# mikro.net
KiCad netlist of a schematic drawn in Altium Designer
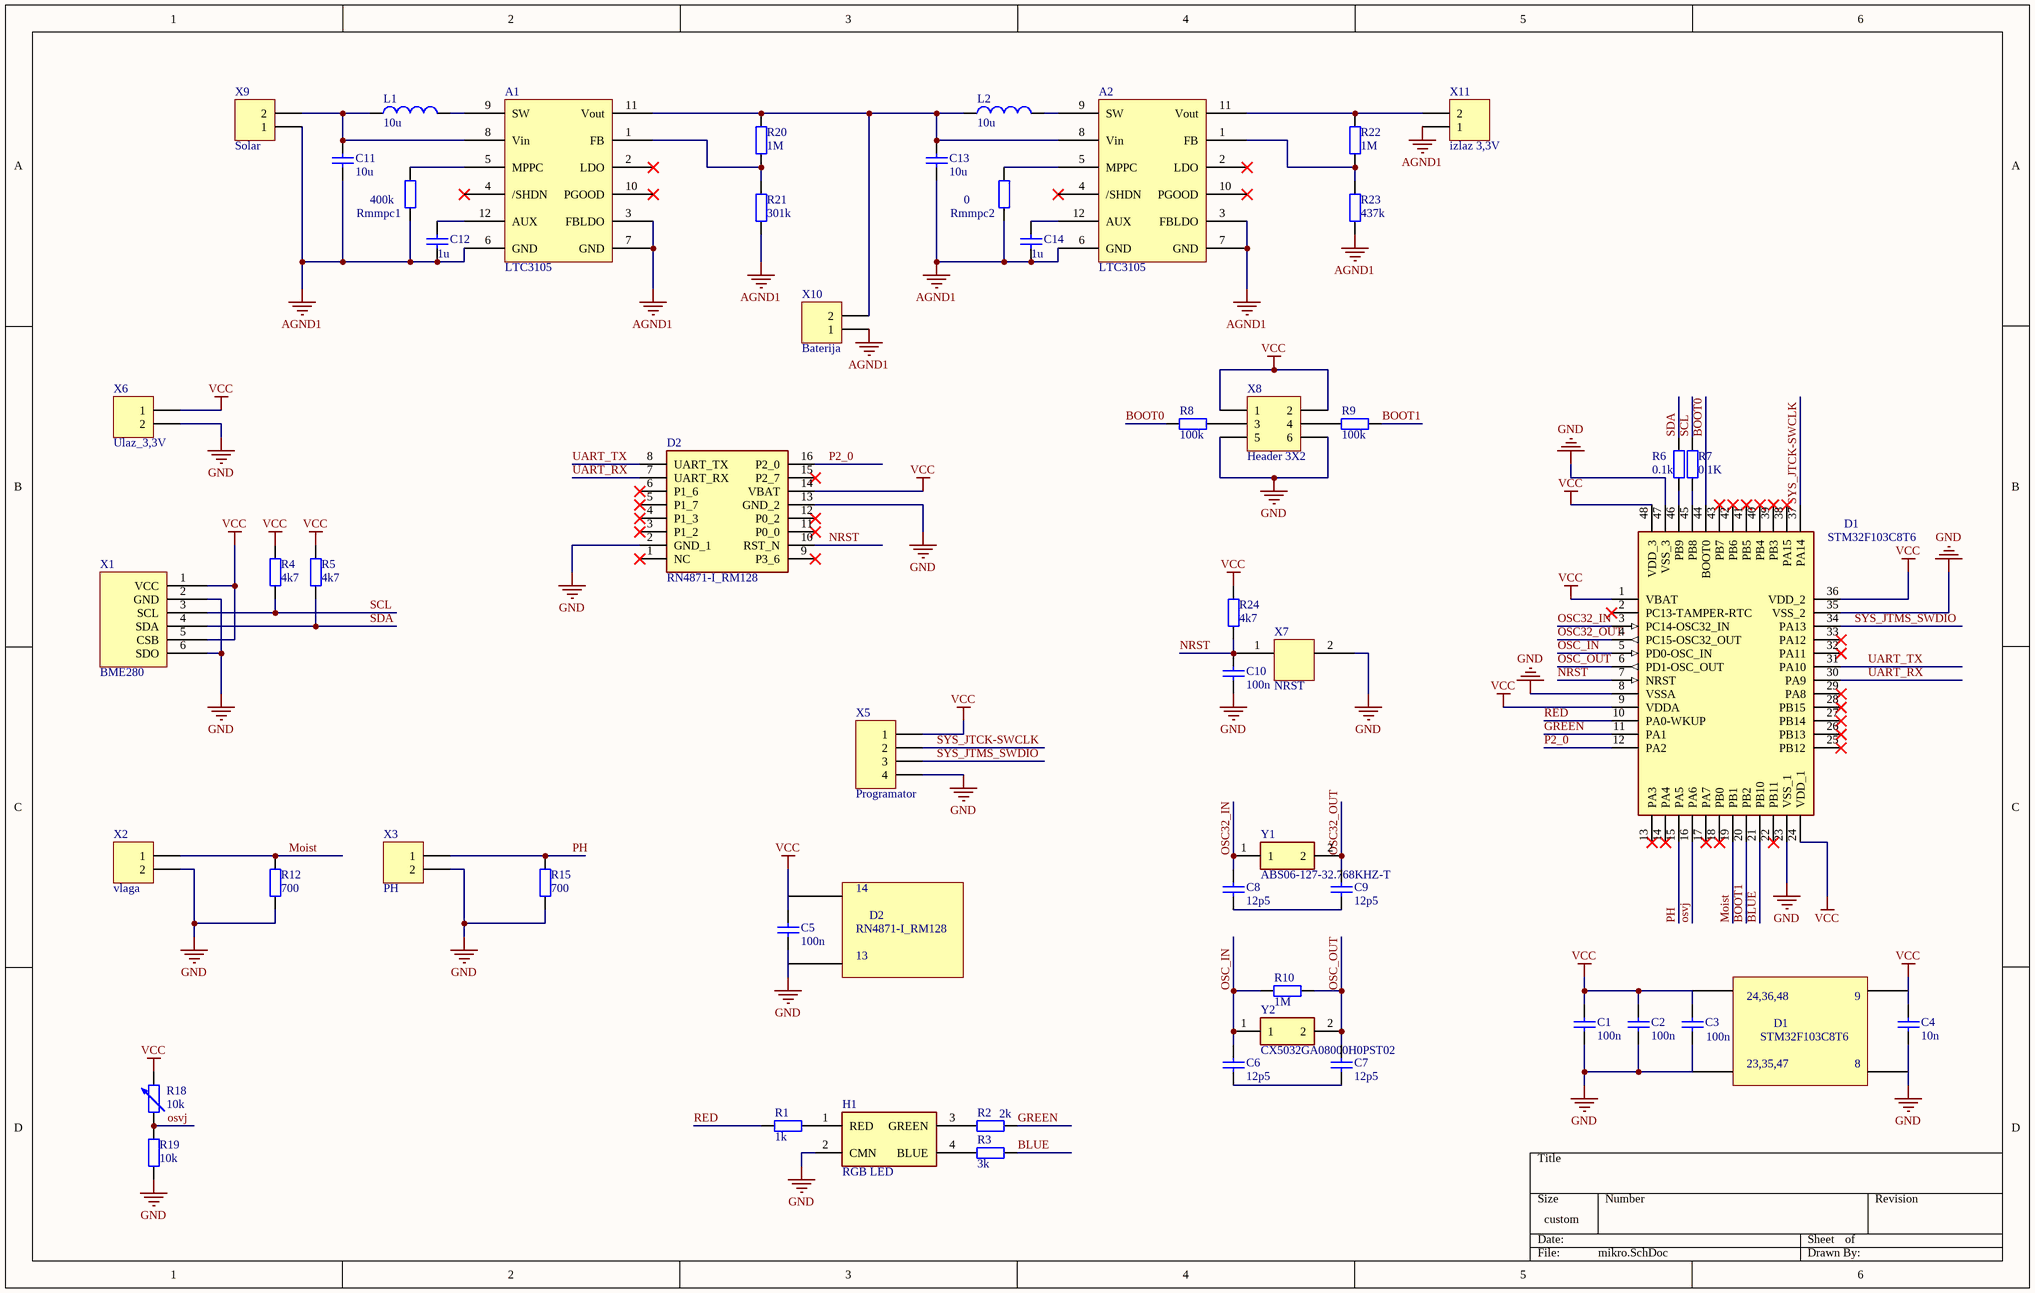
[diagram p0: mikro.SchDoc]

(export (version "E")
  (design (tool "Eeschema 10.0.6"))
  (components
    (comp (ref "A1")
      (value "LTC3105")
      (footprint "SOP65P490X110-12N")
      (libsource (lib "altium-import") (part "root_0_LTC3105_"))
    )
    (comp (ref "A2")
      (value "LTC3105")
      (footprint "SOP65P490X110-12N")
      (libsource (lib "altium-import") (part "root_0_LTC3105_"))
    )
    (comp (ref "C1")
      (value "100n")
      (footprint "6-0805_N")
      (description "Capacitor")
      (fields (field (name "PUBLISHER") "Altium Limited"))
      (libsource (lib "Miscellaneous Devices") (part "Cap"))
    )
    (comp (ref "C2")
      (value "100n")
      (footprint "6-0805_N")
      (description "Capacitor")
      (fields (field (name "PUBLISHER") "Altium Limited"))
      (libsource (lib "Miscellaneous Devices") (part "Cap"))
    )
    (comp (ref "C3")
      (value "100n")
      (footprint "6-0805_N")
      (description "Capacitor")
      (fields (field (name "PUBLISHER") "Altium Limited"))
      (libsource (lib "Miscellaneous Devices") (part "Cap"))
    )
    (comp (ref "C4")
      (value "10n")
      (footprint "6-0805_N")
      (description "Capacitor")
      (fields (field (name "PUBLISHER") "Altium Limited"))
      (libsource (lib "Miscellaneous Devices") (part "Cap"))
    )
    (comp (ref "C5")
      (value "100n")
      (footprint "6-0805_N")
      (description "Capacitor")
      (fields (field (name "PUBLISHER") "Altium Limited"))
      (libsource (lib "Miscellaneous Devices") (part "Cap"))
    )
    (comp (ref "C6")
      (value "12p5")
      (footprint "6-0805_N")
      (description "Capacitor")
      (fields (field (name "PUBLISHER") "Altium Limited"))
      (libsource (lib "Miscellaneous Devices") (part "Cap"))
    )
    (comp (ref "C7")
      (value "12p5")
      (footprint "6-0805_N")
      (description "Capacitor")
      (fields (field (name "PUBLISHER") "Altium Limited"))
      (libsource (lib "Miscellaneous Devices") (part "Cap"))
    )
    (comp (ref "C8")
      (value "12p5")
      (footprint "6-0805_N")
      (description "Capacitor")
      (fields (field (name "PUBLISHER") "Altium Limited"))
      (libsource (lib "Miscellaneous Devices") (part "Cap"))
    )
    (comp (ref "C9")
      (value "12p5")
      (footprint "6-0805_N")
      (description "Capacitor")
      (fields (field (name "PUBLISHER") "Altium Limited"))
      (libsource (lib "Miscellaneous Devices") (part "Cap"))
    )
    (comp (ref "C10")
      (value "100n")
      (footprint "6-0805_N")
      (description "Capacitor")
      (fields (field (name "PUBLISHER") "Altium Limited"))
      (libsource (lib "Miscellaneous Devices") (part "Cap"))
    )
    (comp (ref "C11")
      (value "10u")
      (footprint "6-0805_N")
      (description "Capacitor")
      (fields (field (name "PUBLISHER") "Altium Limited"))
      (libsource (lib "Miscellaneous Devices") (part "Cap"))
    )
    (comp (ref "C12")
      (value "1u")
      (footprint "6-0805_N")
      (description "Capacitor")
      (fields (field (name "PUBLISHER") "Altium Limited"))
      (libsource (lib "Miscellaneous Devices") (part "Cap"))
    )
    (comp (ref "C13")
      (value "10u")
      (footprint "6-0805_N")
      (description "Capacitor")
      (fields (field (name "PUBLISHER") "Altium Limited"))
      (libsource (lib "Miscellaneous Devices") (part "Cap"))
    )
    (comp (ref "C14")
      (value "1u")
      (footprint "6-0805_N")
      (description "Capacitor")
      (fields (field (name "PUBLISHER") "Altium Limited"))
      (libsource (lib "Miscellaneous Devices") (part "Cap"))
    )
    (comp (ref "D1")
      (value "STM32F103C8T6")
      (footprint "SamacSys:QFP50P900X900X160-48N")
      (description "Integrated Circuit")
      (fields
        (field (name "MOUSER PART NUMBER") "511-STM32F103C8T6")
        (field (name "RS PART NUMBER") "0402279P")
      )
      (libsource (lib "*") (part "STM32F103C8T6"))
    )
    (comp (ref "D2")
      (value "RN4871-I_RM128")
      (footprint "SamacSys:RN4871")
      (description "Integrated Circuit")
      (fields
        (field (name "MANUFACTURER_PART_NUMBER") "RN4871-I/RM128")
        (field (name "MOUSER PART NUMBER") "579-RN4871-I/RM128")
      )
      (libsource (lib "altium-import") (part "root_2_mirrored_RN4871-I_RM128_"))
    )
    (comp (ref "H1")
      (value "RGB LED")
      (footprint "HV5RGB25")
      (description "LED")
      (fields
        (field (name "MANUFACTURER_PART_NUMBER") "APTF1616LSEEZGKQBKC")
        (field (name "MOUSER PART NUMBER") "604-APTF1616LSEEZGKQ")
      )
      (libsource (lib "altium-import") (part "root_0_APTF1616LSEEZGKQBKC_"))
    )
    (comp (ref "L1")
      (value "10u")
      (footprint "6-0805_N")
      (description "Inductor")
      (fields (field (name "PUBLISHER") "Altium Limited"))
      (libsource (lib "Miscellaneous Devices") (part "Inductor"))
    )
    (comp (ref "L2")
      (value "10u")
      (footprint "6-0805_N")
      (description "Inductor")
      (fields (field (name "PUBLISHER") "Altium Limited"))
      (libsource (lib "Miscellaneous Devices") (part "Inductor"))
    )
    (comp (ref "R1")
      (value "1k")
      (footprint "6-0805_N")
      (description "Resistor")
      (fields (field (name "PUBLISHER") "Altium Limited"))
      (libsource (lib "") (part "Res2_3"))
    )
    (comp (ref "R2")
      (value "2k")
      (footprint "6-0805_N")
      (description "Resistor")
      (fields (field (name "PUBLISHER") "Altium Limited"))
      (libsource (lib "") (part "Res2_3"))
    )
    (comp (ref "R3")
      (value "3k")
      (footprint "6-0805_N")
      (description "Resistor")
      (fields (field (name "PUBLISHER") "Altium Limited"))
      (libsource (lib "") (part "Res2_3"))
    )
    (comp (ref "R4")
      (value "4k7")
      (footprint "6-0805_N")
      (description "Resistor")
      (fields (field (name "PUBLISHER") "Altium Limited"))
      (libsource (lib "") (part "Res2_1"))
    )
    (comp (ref "R5")
      (value "4k7")
      (footprint "6-0805_N")
      (description "Resistor")
      (fields (field (name "PUBLISHER") "Altium Limited"))
      (libsource (lib "") (part "Res2_1"))
    )
    (comp (ref "R6")
      (value "0.1k")
      (footprint "6-0805_N")
      (description "Resistor")
      (fields (field (name "PUBLISHER") "Altium Limited"))
      (libsource (lib "") (part "Res2_1"))
    )
    (comp (ref "R7")
      (value "0.1K")
      (footprint "6-0805_N")
      (description "Resistor")
      (fields (field (name "PUBLISHER") "Altium Limited"))
      (libsource (lib "") (part "Res2_1"))
    )
    (comp (ref "R8")
      (value "100k")
      (footprint "6-0805_N")
      (description "Resistor")
      (fields (field (name "PUBLISHER") "Altium Limited"))
      (libsource (lib "") (part "Res2_2"))
    )
    (comp (ref "R9")
      (value "100k")
      (footprint "6-0805_N")
      (description "Resistor")
      (fields (field (name "PUBLISHER") "Altium Limited"))
      (libsource (lib "") (part "Res2_2"))
    )
    (comp (ref "R10")
      (value "1M")
      (footprint "6-0805_N")
      (description "Resistor")
      (fields (field (name "PUBLISHER") "Altium Limited"))
      (libsource (lib "") (part "Res2_3"))
    )
    (comp (ref "R12")
      (value "700")
      (footprint "6-0805_N")
      (description "Resistor")
      (fields (field (name "PUBLISHER") "Altium Limited"))
      (libsource (lib "Miscellaneous Devices") (part "Res2"))
    )
    (comp (ref "R15")
      (value "700")
      (footprint "6-0805_N")
      (description "Resistor")
      (fields (field (name "PUBLISHER") "Altium Limited"))
      (libsource (lib "Miscellaneous Devices") (part "Res2"))
    )
    (comp (ref "R18")
      (value "10k")
      (footprint "HDR1X2")
      (description "Variable Resistor")
      (fields (field (name "PUBLISHER") "Altium Limited"))
      (libsource (lib "Miscellaneous Devices") (part "Res Adj2"))
    )
    (comp (ref "R19")
      (value "10k")
      (footprint "6-0805_N")
      (description "Resistor")
      (fields (field (name "PUBLISHER") "Altium Limited"))
      (libsource (lib "") (part "Res2_1"))
    )
    (comp (ref "R20")
      (value "1M")
      (footprint "6-0805_N")
      (description "Resistor")
      (fields (field (name "PUBLISHER") "Altium Limited"))
      (libsource (lib "") (part "Res2_1"))
    )
    (comp (ref "R21")
      (value "301k")
      (footprint "6-0805_N")
      (description "Resistor")
      (fields (field (name "PUBLISHER") "Altium Limited"))
      (libsource (lib "Miscellaneous Devices") (part "Res2"))
    )
    (comp (ref "R22")
      (value "1M")
      (footprint "6-0805_N")
      (description "Resistor")
      (fields (field (name "PUBLISHER") "Altium Limited"))
      (libsource (lib "") (part "Res2_1"))
    )
    (comp (ref "R23")
      (value "437k")
      (footprint "6-0805_N")
      (description "Resistor")
      (fields (field (name "PUBLISHER") "Altium Limited"))
      (libsource (lib "Miscellaneous Devices") (part "Res2"))
    )
    (comp (ref "R24")
      (value "4k7")
      (footprint "6-0805_N")
      (description "Resistor")
      (fields (field (name "PUBLISHER") "Altium Limited"))
      (libsource (lib "Miscellaneous Devices") (part "Res2"))
    )
    (comp (ref "Rmmpc1")
      (value "400k")
      (footprint "6-0805_N")
      (description "Resistor")
      (fields (field (name "PUBLISHER") "Altium Limited"))
      (libsource (lib "") (part "Res2_1"))
    )
    (comp (ref "Rmmpc2")
      (value "0")
      (footprint "6-0805_N")
      (description "Resistor")
      (fields (field (name "PUBLISHER") "Altium Limited"))
      (libsource (lib "") (part "Res2_1"))
    )
    (comp (ref "X1")
      (value "BME280")
      (footprint "HDR1X6")
      (libsource (lib "altium-import") (part "root_0_BME280_"))
    )
    (comp (ref "X2")
      (value "vlaga")
      (footprint "HDR1X2")
      (description "Header, 2-Pin")
      (fields (field (name "PUBLISHER") "Altium Limited"))
      (libsource (lib "Miscellaneous Connectors") (part "Header 2"))
    )
    (comp (ref "X3")
      (value "PH")
      (footprint "HDR1X2")
      (description "Header, 2-Pin")
      (fields (field (name "PUBLISHER") "Altium Limited"))
      (libsource (lib "Miscellaneous Connectors") (part "Header 2"))
    )
    (comp (ref "X5")
      (value "Programator")
      (footprint "HDR1X4")
      (description "Header, 4-Pin")
      (fields (field (name "PUBLISHER") "Altium Limited"))
      (libsource (lib "Miscellaneous Connectors") (part "Header 4"))
    )
    (comp (ref "X6")
      (value "Ulaz_3,3V")
      (footprint "HDR1X2")
      (description "Header, 2-Pin")
      (fields (field (name "PUBLISHER") "Altium Limited"))
      (libsource (lib "Miscellaneous Connectors") (part "Header 2"))
    )
    (comp (ref "X7") (value "NRST") (libsource (lib "altium-import") (part "root_1_jumper_")))
    (comp (ref "X8")
      (value "Header 3X2")
      (footprint "HDR2X3")
      (description "Header, 3-Pin, Dual row")
      (fields (field (name "PUBLISHER") "Altium Limited"))
      (libsource (lib "Miscellaneous Connectors") (part "Header 3X2"))
    )
    (comp (ref "X9")
      (value "Solar")
      (footprint "HDR1X2")
      (description "Header, 2-Pin")
      (fields (field (name "PUBLISHER") "Altium Limited"))
      (libsource (lib "") (part "Header 2_2"))
    )
    (comp (ref "X10")
      (value "Baterija")
      (footprint "HDR1X2")
      (description "Header, 2-Pin")
      (fields (field (name "PUBLISHER") "Altium Limited"))
      (libsource (lib "") (part "Header 2_2"))
    )
    (comp (ref "X11")
      (value "izlaz 3,3V")
      (footprint "HDR1X2")
      (description "Header, 2-Pin")
      (fields (field (name "PUBLISHER") "Altium Limited"))
      (libsource (lib "") (part "Header 2_1"))
    )
    (comp (ref "Y1")
      (value "ABS06-127-32.768KHZ-T")
      (footprint "SamacSys:ABS0612732768KHZT")
      (description "Crystal or Oscillator")
      (fields
        (field (name "MOUSER PART NUMBER") "815-ABS0612732.768KT")
        (field (name "RS PART NUMBER") "1753472P")
      )
      (libsource (lib "*") (part "ABS06-127-32.768KHZ-T"))
    )
    (comp (ref "Y2")
      (value "CX5032GA08000H0PST02")
      (footprint "SamacSys:CX5032GA08000H0PST02")
      (description "Crystal or Oscillator")
      (fields (field (name "MOUSER PART NUMBER") "581-CX5032GA08H0PST"))
      (libsource (lib "*") (part "CX5032GA08000H0PST02"))
    )
  )
  (nets
    (net (code "1") (name "/BLUE") (class "Default")
      (node (ref "D1") (pin "21") (pinfunction "PB10_21") (pintype "passive"))
      (node (ref "R3") (pin "2") (pinfunction "2_2") (pintype "passive"))
    )
    (net (code "2") (name "/BOOT0") (class "Default")
      (node (ref "D1") (pin "44") (pinfunction "BOOT0_44") (pintype "passive"))
      (node (ref "R8") (pin "2") (pinfunction "2_2") (pintype "passive"))
    )
    (net (code "3") (name "/BOOT1") (class "Default")
      (node (ref "D1") (pin "20") (pinfunction "PB2_20") (pintype "passive"))
      (node (ref "R9") (pin "1") (pinfunction "1_1") (pintype "passive"))
    )
    (net (code "4") (name "/GREEN") (class "Default")
      (node (ref "D1") (pin "11") (pinfunction "PA1_11") (pintype "passive"))
      (node (ref "R2") (pin "2") (pinfunction "2_2") (pintype "passive"))
    )
    (net (code "5") (name "/Moist") (class "Default")
      (node (ref "D1") (pin "19") (pinfunction "PB1_19") (pintype "passive"))
      (node (ref "R12") (pin "1") (pinfunction "1_1") (pintype "passive"))
      (node (ref "X2") (pin "1") (pinfunction "1_1") (pintype "passive"))
    )
    (net (code "6") (name "/NRST") (class "Default")
      (node (ref "C10") (pin "2") (pinfunction "2_2") (pintype "passive"))
      (node (ref "D1") (pin "7") (pinfunction "NRST_7") (pintype "input"))
      (node (ref "D2") (pin "10") (pinfunction "RST_N_10") (pintype "passive"))
      (node (ref "R24") (pin "2") (pinfunction "2_2") (pintype "passive"))
      (node (ref "X7") (pin "1") (pintype "passive"))
    )
    (net (code "7") (name "/OSC32_IN") (class "Default")
      (node (ref "C8") (pin "2") (pinfunction "2_2") (pintype "passive"))
      (node (ref "D1") (pin "3") (pinfunction "PC14-OSC32_IN_3") (pintype "input"))
      (node (ref "Y1") (pin "1") (pinfunction "1_1") (pintype "passive"))
    )
    (net (code "8") (name "/OSC32_OUT") (class "Default")
      (node (ref "C9") (pin "2") (pinfunction "2_2") (pintype "passive"))
      (node (ref "D1") (pin "4") (pinfunction "PC15-OSC32_OUT_4") (pintype "output"))
      (node (ref "Y1") (pin "2") (pinfunction "2_2") (pintype "passive"))
    )
    (net (code "9") (name "/OSC_IN") (class "Default")
      (node (ref "C6") (pin "2") (pinfunction "2_2") (pintype "passive"))
      (node (ref "D1") (pin "5") (pinfunction "PD0-OSC_IN_5") (pintype "input"))
      (node (ref "R10") (pin "1") (pinfunction "1_1") (pintype "passive"))
      (node (ref "Y2") (pin "1") (pinfunction "1_1") (pintype "passive"))
    )
    (net (code "10") (name "/OSC_OUT") (class "Default")
      (node (ref "C7") (pin "2") (pinfunction "2_2") (pintype "passive"))
      (node (ref "D1") (pin "6") (pinfunction "PD1-OSC_OUT_6") (pintype "output"))
      (node (ref "R10") (pin "2") (pinfunction "2_2") (pintype "passive"))
      (node (ref "Y2") (pin "2") (pinfunction "2_2") (pintype "passive"))
    )
    (net (code "11") (name "/P2_0") (class "Default")
      (node (ref "D1") (pin "12") (pinfunction "PA2_12") (pintype "passive"))
      (node (ref "D2") (pin "16") (pinfunction "P2_0_16") (pintype "passive"))
    )
    (net (code "12") (name "/PH") (class "Default")
      (node (ref "D1") (pin "15") (pinfunction "PA5_15") (pintype "passive"))
      (node (ref "R15") (pin "1") (pinfunction "1_1") (pintype "passive"))
      (node (ref "X3") (pin "1") (pinfunction "1_1") (pintype "passive"))
    )
    (net (code "13") (name "/RED") (class "Default")
      (node (ref "D1") (pin "10") (pinfunction "PA0-WKUP_10") (pintype "passive"))
      (node (ref "R1") (pin "1") (pinfunction "1_1") (pintype "passive"))
    )
    (net (code "14") (name "/SCL") (class "Default")
      (node (ref "R4") (pin "1") (pinfunction "1_1") (pintype "passive"))
      (node (ref "R7") (pin "2") (pinfunction "2_2") (pintype "passive"))
      (node (ref "X1") (pin "3") (pinfunction "SCL_3") (pintype "passive"))
    )
    (net (code "15") (name "/SDA") (class "Default")
      (node (ref "R5") (pin "1") (pinfunction "1_1") (pintype "passive"))
      (node (ref "R6") (pin "2") (pinfunction "2_2") (pintype "passive"))
      (node (ref "X1") (pin "4") (pinfunction "SDA_4") (pintype "passive"))
    )
    (net (code "16") (name "/SYS_JTCK-SWCLK") (class "Default")
      (node (ref "D1") (pin "37") (pinfunction "PA14_37") (pintype "passive"))
      (node (ref "X5") (pin "2") (pinfunction "2_2") (pintype "passive"))
    )
    (net (code "17") (name "/SYS_JTMS_SWDIO") (class "Default")
      (node (ref "D1") (pin "34") (pinfunction "PA13_34") (pintype "passive"))
      (node (ref "X5") (pin "3") (pinfunction "3_3") (pintype "passive"))
    )
    (net (code "18") (name "/UART_RX") (class "Default")
      (node (ref "D1") (pin "30") (pinfunction "PA9_30") (pintype "passive"))
      (node (ref "D2") (pin "7") (pinfunction "UART_RX_7") (pintype "passive"))
    )
    (net (code "19") (name "/UART_TX") (class "Default")
      (node (ref "D1") (pin "31") (pinfunction "PA10_31") (pintype "passive"))
      (node (ref "D2") (pin "8") (pinfunction "UART_TX_8") (pintype "passive"))
    )
    (net (code "20") (name "/osvj") (class "Default")
      (node (ref "D1") (pin "16") (pinfunction "PA6_16") (pintype "passive"))
      (node (ref "R18") (pin "1") (pinfunction "1_1") (pintype "passive"))
      (node (ref "R19") (pin "2") (pinfunction "2_2") (pintype "passive"))
    )
    (net (code "21") (name "AGND1") (class "Default")
      (node (ref "A1") (pin "3") (pinfunction "FBLDO_3") (pintype "passive"))
      (node (ref "A1") (pin "6") (pinfunction "GND_6") (pintype "passive"))
      (node (ref "A1") (pin "7") (pinfunction "GND_7") (pintype "passive"))
      (node (ref "A2") (pin "3") (pinfunction "FBLDO_3") (pintype "passive"))
      (node (ref "A2") (pin "6") (pinfunction "GND_6") (pintype "passive"))
      (node (ref "A2") (pin "7") (pinfunction "GND_7") (pintype "passive"))
      (node (ref "C11") (pin "1") (pinfunction "1_1") (pintype "passive"))
      (node (ref "C12") (pin "1") (pinfunction "1_1") (pintype "passive"))
      (node (ref "C13") (pin "1") (pinfunction "1_1") (pintype "passive"))
      (node (ref "C14") (pin "1") (pinfunction "1_1") (pintype "passive"))
      (node (ref "R21") (pin "2") (pinfunction "2_2") (pintype "passive"))
      (node (ref "R23") (pin "2") (pinfunction "2_2") (pintype "passive"))
      (node (ref "Rmmpc1") (pin "1") (pinfunction "1_1") (pintype "passive"))
      (node (ref "Rmmpc2") (pin "1") (pinfunction "1_1") (pintype "passive"))
      (node (ref "X10") (pin "1") (pinfunction "1_1") (pintype "passive"))
      (node (ref "X11") (pin "1") (pinfunction "1_1") (pintype "passive"))
      (node (ref "X9") (pin "1") (pinfunction "1_1") (pintype "passive"))
    )
    (net (code "22") (name "GND") (class "Default")
      (node (ref "C1") (pin "1") (pinfunction "1_1") (pintype "passive"))
      (node (ref "C10") (pin "1") (pinfunction "1_1") (pintype "passive"))
      (node (ref "C2") (pin "1") (pinfunction "1_1") (pintype "passive"))
      (node (ref "C3") (pin "1") (pinfunction "1_1") (pintype "passive"))
      (node (ref "C4") (pin "1") (pinfunction "1_1") (pintype "passive"))
      (node (ref "C5") (pin "1") (pinfunction "1_1") (pintype "passive"))
      (node (ref "D1") (pin "23") (pinfunction "VSS_1_23") (pintype "power_in"))
      (node (ref "D1") (pin "35") (pinfunction "VSS_2_35") (pintype "power_in"))
      (node (ref "D1") (pin "47") (pinfunction "VSS_3_47") (pintype "power_in"))
      (node (ref "D1") (pin "8") (pinfunction "VSSA_8") (pintype "power_in"))
      (node (ref "D2") (pin "13") (pinfunction "GND_2_13") (pintype "passive"))
      (node (ref "D2") (pin "2") (pinfunction "GND_1_2") (pintype "passive"))
      (node (ref "H1") (pin "2") (pinfunction "CMN_2") (pintype "passive"))
      (node (ref "R12") (pin "2") (pinfunction "2_2") (pintype "passive"))
      (node (ref "R15") (pin "2") (pinfunction "2_2") (pintype "passive"))
      (node (ref "R19") (pin "1") (pinfunction "1_1") (pintype "passive"))
      (node (ref "X1") (pin "2") (pinfunction "GND_2") (pintype "power_in"))
      (node (ref "X1") (pin "6") (pinfunction "SDO_6") (pintype "power_in"))
      (node (ref "X2") (pin "2") (pinfunction "2_2") (pintype "passive"))
      (node (ref "X3") (pin "2") (pinfunction "2_2") (pintype "passive"))
      (node (ref "X5") (pin "4") (pinfunction "4_4") (pintype "passive"))
      (node (ref "X6") (pin "2") (pinfunction "2_2") (pintype "passive"))
      (node (ref "X7") (pin "2") (pinfunction "10_2") (pintype "power_in"))
      (node (ref "X8") (pin "5") (pinfunction "5_5") (pintype "passive"))
      (node (ref "X8") (pin "6") (pinfunction "6_6") (pintype "passive"))
    )
    (net (code "23") (name "Net-(A1-AUX)") (class "Default")
      (node (ref "A1") (pin "12") (pinfunction "AUX_12") (pintype "passive"))
      (node (ref "C12") (pin "2") (pinfunction "2_2") (pintype "passive"))
    )
    (net (code "24") (name "Net-(A1-FB)") (class "Default")
      (node (ref "A1") (pin "1") (pinfunction "FB_1") (pintype "passive"))
      (node (ref "R20") (pin "1") (pinfunction "1_1") (pintype "passive"))
      (node (ref "R21") (pin "1") (pinfunction "1_1") (pintype "passive"))
    )
    (net (code "25") (name "Net-(A1-MPPC)") (class "Default")
      (node (ref "A1") (pin "5") (pinfunction "MPPC_5") (pintype "passive"))
      (node (ref "Rmmpc1") (pin "2") (pinfunction "2_2") (pintype "passive"))
    )
    (net (code "26") (name "Net-(A1-SW)") (class "Default")
      (node (ref "A1") (pin "9") (pinfunction "SW_9") (pintype "passive"))
      (node (ref "L1") (pin "2") (pinfunction "2_2") (pintype "passive"))
    )
    (net (code "27") (name "Net-(A1-Vin)") (class "Default")
      (node (ref "A1") (pin "8") (pinfunction "Vin_8") (pintype "passive"))
      (node (ref "C11") (pin "2") (pinfunction "2_2") (pintype "passive"))
      (node (ref "L1") (pin "1") (pinfunction "1_1") (pintype "passive"))
      (node (ref "X9") (pin "2") (pinfunction "2_2") (pintype "passive"))
    )
    (net (code "28") (name "Net-(A1-Vout)") (class "Default")
      (node (ref "A1") (pin "11") (pinfunction "Vout_11") (pintype "passive"))
      (node (ref "A2") (pin "8") (pinfunction "Vin_8") (pintype "passive"))
      (node (ref "C13") (pin "2") (pinfunction "2_2") (pintype "passive"))
      (node (ref "L2") (pin "1") (pinfunction "1_1") (pintype "passive"))
      (node (ref "R20") (pin "2") (pinfunction "2_2") (pintype "passive"))
      (node (ref "X10") (pin "2") (pinfunction "2_2") (pintype "passive"))
    )
    (net (code "29") (name "Net-(A2-AUX)") (class "Default")
      (node (ref "A2") (pin "12") (pinfunction "AUX_12") (pintype "passive"))
      (node (ref "C14") (pin "2") (pinfunction "2_2") (pintype "passive"))
    )
    (net (code "30") (name "Net-(A2-FB)") (class "Default")
      (node (ref "A2") (pin "1") (pinfunction "FB_1") (pintype "passive"))
      (node (ref "R22") (pin "1") (pinfunction "1_1") (pintype "passive"))
      (node (ref "R23") (pin "1") (pinfunction "1_1") (pintype "passive"))
    )
    (net (code "31") (name "Net-(A2-MPPC)") (class "Default")
      (node (ref "A2") (pin "5") (pinfunction "MPPC_5") (pintype "passive"))
      (node (ref "Rmmpc2") (pin "2") (pinfunction "2_2") (pintype "passive"))
    )
    (net (code "32") (name "Net-(A2-SW)") (class "Default")
      (node (ref "A2") (pin "9") (pinfunction "SW_9") (pintype "passive"))
      (node (ref "L2") (pin "2") (pinfunction "2_2") (pintype "passive"))
    )
    (net (code "33") (name "Net-(A2-Vout)") (class "Default")
      (node (ref "A2") (pin "11") (pinfunction "Vout_11") (pintype "passive"))
      (node (ref "R22") (pin "2") (pinfunction "2_2") (pintype "passive"))
      (node (ref "X11") (pin "2") (pinfunction "2_2") (pintype "passive"))
    )
    (net (code "34") (name "Net-(C6-Pad1)") (class "Default")
      (node (ref "C6") (pin "1") (pinfunction "1_1") (pintype "passive"))
      (node (ref "C7") (pin "1") (pinfunction "1_1") (pintype "passive"))
    )
    (net (code "35") (name "Net-(C8-Pad1)") (class "Default")
      (node (ref "C8") (pin "1") (pinfunction "1_1") (pintype "passive"))
      (node (ref "C9") (pin "1") (pinfunction "1_1") (pintype "passive"))
    )
    (net (code "36") (name "Net-(D1-PB8)") (class "Default")
      (node (ref "D1") (pin "45") (pinfunction "PB8_45") (pintype "passive"))
      (node (ref "R7") (pin "1") (pinfunction "1_1") (pintype "passive"))
    )
    (net (code "37") (name "Net-(D1-PB9)") (class "Default")
      (node (ref "D1") (pin "46") (pinfunction "PB9_46") (pintype "passive"))
      (node (ref "R6") (pin "1") (pinfunction "1_1") (pintype "passive"))
    )
    (net (code "38") (name "Net-(H1-BLUE)") (class "Default")
      (node (ref "H1") (pin "4") (pinfunction "BLUE_4") (pintype "passive"))
      (node (ref "R3") (pin "1") (pinfunction "1_1") (pintype "passive"))
    )
    (net (code "39") (name "Net-(H1-GREEN)") (class "Default")
      (node (ref "H1") (pin "3") (pinfunction "GREEN_3") (pintype "passive"))
      (node (ref "R2") (pin "1") (pinfunction "1_1") (pintype "passive"))
    )
    (net (code "40") (name "Net-(H1-RED)") (class "Default")
      (node (ref "H1") (pin "1") (pinfunction "RED_1") (pintype "passive"))
      (node (ref "R1") (pin "2") (pinfunction "2_2") (pintype "passive"))
    )
    (net (code "41") (name "Net-(R8-Pad1)") (class "Default")
      (node (ref "R8") (pin "1") (pinfunction "1_1") (pintype "passive"))
      (node (ref "X8") (pin "3") (pinfunction "3_3") (pintype "passive"))
    )
    (net (code "42") (name "Net-(R9-Pad2)") (class "Default")
      (node (ref "R9") (pin "2") (pinfunction "2_2") (pintype "passive"))
      (node (ref "X8") (pin "4") (pinfunction "4_4") (pintype "passive"))
    )
    (net (code "43") (name "VCC") (class "Default")
      (node (ref "C1") (pin "2") (pinfunction "2_2") (pintype "passive"))
      (node (ref "C2") (pin "2") (pinfunction "2_2") (pintype "passive"))
      (node (ref "C3") (pin "2") (pinfunction "2_2") (pintype "passive"))
      (node (ref "C4") (pin "2") (pinfunction "2_2") (pintype "passive"))
      (node (ref "C5") (pin "2") (pinfunction "2_2") (pintype "passive"))
      (node (ref "D1") (pin "1") (pinfunction "VBAT_1") (pintype "passive"))
      (node (ref "D1") (pin "24") (pinfunction "VDD_1_24") (pintype "power_in"))
      (node (ref "D1") (pin "36") (pinfunction "VDD_2_36") (pintype "power_in"))
      (node (ref "D1") (pin "48") (pinfunction "VDD_3_48") (pintype "power_in"))
      (node (ref "D1") (pin "9") (pinfunction "VDDA_9") (pintype "power_in"))
      (node (ref "D2") (pin "14") (pinfunction "VBAT_14") (pintype "passive"))
      (node (ref "R18") (pin "2") (pinfunction "2_2") (pintype "passive"))
      (node (ref "R24") (pin "1") (pinfunction "1_1") (pintype "passive"))
      (node (ref "R4") (pin "2") (pinfunction "2_2") (pintype "passive"))
      (node (ref "R5") (pin "2") (pinfunction "2_2") (pintype "passive"))
      (node (ref "X1") (pin "1") (pinfunction "VCC_1") (pintype "power_in"))
      (node (ref "X1") (pin "5") (pinfunction "CSB_5") (pintype "passive"))
      (node (ref "X5") (pin "1") (pinfunction "1_1") (pintype "passive"))
      (node (ref "X6") (pin "1") (pinfunction "1_1") (pintype "passive"))
      (node (ref "X8") (pin "1") (pinfunction "1_1") (pintype "passive"))
      (node (ref "X8") (pin "2") (pinfunction "2_2") (pintype "passive"))
    )
    (net (code "44") (name "unconnected-(A1-LDO-Pad2)") (class "Default")
      (node (ref "A1") (pin "2") (pinfunction "LDO_2") (pintype "passive+no_connect"))
    )
    (net (code "45") (name "unconnected-(A1-PGOOD-Pad10)") (class "Default")
      (node (ref "A1") (pin "10") (pinfunction "PGOOD_10") (pintype "passive+no_connect"))
    )
    (net (code "46") (name "unconnected-(A1-{slash}SHDN-Pad4)") (class "Default")
      (node (ref "A1") (pin "4") (pinfunction "/SHDN_4") (pintype "passive+no_connect"))
    )
    (net (code "47") (name "unconnected-(A2-LDO-Pad2)") (class "Default")
      (node (ref "A2") (pin "2") (pinfunction "LDO_2") (pintype "passive+no_connect"))
    )
    (net (code "48") (name "unconnected-(A2-PGOOD-Pad10)") (class "Default")
      (node (ref "A2") (pin "10") (pinfunction "PGOOD_10") (pintype "passive+no_connect"))
    )
    (net (code "49") (name "unconnected-(A2-{slash}SHDN-Pad4)") (class "Default")
      (node (ref "A2") (pin "4") (pinfunction "/SHDN_4") (pintype "passive+no_connect"))
    )
    (net (code "50") (name "unconnected-(D1-PA3-Pad13)") (class "Default")
      (node (ref "D1") (pin "13") (pinfunction "PA3_13") (pintype "passive+no_connect"))
    )
    (net (code "51") (name "unconnected-(D1-PA4-Pad14)") (class "Default")
      (node (ref "D1") (pin "14") (pinfunction "PA4_14") (pintype "passive+no_connect"))
    )
    (net (code "52") (name "unconnected-(D1-PA7-Pad17)") (class "Default")
      (node (ref "D1") (pin "17") (pinfunction "PA7_17") (pintype "passive+no_connect"))
    )
    (net (code "53") (name "unconnected-(D1-PA8-Pad29)") (class "Default")
      (node (ref "D1") (pin "29") (pinfunction "PA8_29") (pintype "passive+no_connect"))
    )
    (net (code "54") (name "unconnected-(D1-PA11-Pad32)") (class "Default")
      (node (ref "D1") (pin "32") (pinfunction "PA11_32") (pintype "passive+no_connect"))
    )
    (net (code "55") (name "unconnected-(D1-PA12-Pad33)") (class "Default")
      (node (ref "D1") (pin "33") (pinfunction "PA12_33") (pintype "passive+no_connect"))
    )
    (net (code "56") (name "unconnected-(D1-PA15-Pad38)") (class "Default")
      (node (ref "D1") (pin "38") (pinfunction "PA15_38") (pintype "passive+no_connect"))
    )
    (net (code "57") (name "unconnected-(D1-PB0-Pad18)") (class "Default")
      (node (ref "D1") (pin "18") (pinfunction "PB0_18") (pintype "passive+no_connect"))
    )
    (net (code "58") (name "unconnected-(D1-PB3-Pad39)") (class "Default")
      (node (ref "D1") (pin "39") (pinfunction "PB3_39") (pintype "passive+no_connect"))
    )
    (net (code "59") (name "unconnected-(D1-PB4-Pad40)") (class "Default")
      (node (ref "D1") (pin "40") (pinfunction "PB4_40") (pintype "passive+no_connect"))
    )
    (net (code "60") (name "unconnected-(D1-PB5-Pad41)") (class "Default")
      (node (ref "D1") (pin "41") (pinfunction "PB5_41") (pintype "passive+no_connect"))
    )
    (net (code "61") (name "unconnected-(D1-PB6-Pad42)") (class "Default")
      (node (ref "D1") (pin "42") (pinfunction "PB6_42") (pintype "passive+no_connect"))
    )
    (net (code "62") (name "unconnected-(D1-PB7-Pad43)") (class "Default")
      (node (ref "D1") (pin "43") (pinfunction "PB7_43") (pintype "passive+no_connect"))
    )
    (net (code "63") (name "unconnected-(D1-PB11-Pad22)") (class "Default")
      (node (ref "D1") (pin "22") (pinfunction "PB11_22") (pintype "passive+no_connect"))
    )
    (net (code "64") (name "unconnected-(D1-PB12-Pad25)") (class "Default")
      (node (ref "D1") (pin "25") (pinfunction "PB12_25") (pintype "passive+no_connect"))
    )
    (net (code "65") (name "unconnected-(D1-PB13-Pad26)") (class "Default")
      (node (ref "D1") (pin "26") (pinfunction "PB13_26") (pintype "passive+no_connect"))
    )
    (net (code "66") (name "unconnected-(D1-PB14-Pad27)") (class "Default")
      (node (ref "D1") (pin "27") (pinfunction "PB14_27") (pintype "passive+no_connect"))
    )
    (net (code "67") (name "unconnected-(D1-PB15-Pad28)") (class "Default")
      (node (ref "D1") (pin "28") (pinfunction "PB15_28") (pintype "passive+no_connect"))
    )
    (net (code "68") (name "unconnected-(D1-PC13-TAMPER-RTC-Pad2)") (class "Default")
      (node (ref "D1") (pin "2") (pinfunction "PC13-TAMPER-RTC_2") (pintype "passive+no_connect"))
    )
    (net (code "69") (name "unconnected-(D2-NC-Pad1)") (class "Default")
      (node (ref "D2") (pin "1") (pinfunction "NC_1") (pintype "passive+no_connect"))
    )
    (net (code "70") (name "unconnected-(D2-P0_0-Pad11)") (class "Default")
      (node (ref "D2") (pin "11") (pinfunction "P0_0_11") (pintype "passive+no_connect"))
    )
    (net (code "71") (name "unconnected-(D2-P0_2-Pad12)") (class "Default")
      (node (ref "D2") (pin "12") (pinfunction "P0_2_12") (pintype "passive+no_connect"))
    )
    (net (code "72") (name "unconnected-(D2-P1_2-Pad3)") (class "Default")
      (node (ref "D2") (pin "3") (pinfunction "P1_2_3") (pintype "passive+no_connect"))
    )
    (net (code "73") (name "unconnected-(D2-P1_3-Pad4)") (class "Default")
      (node (ref "D2") (pin "4") (pinfunction "P1_3_4") (pintype "passive+no_connect"))
    )
    (net (code "74") (name "unconnected-(D2-P1_6-Pad6)") (class "Default")
      (node (ref "D2") (pin "6") (pinfunction "P1_6_6") (pintype "passive+no_connect"))
    )
    (net (code "75") (name "unconnected-(D2-P1_7-Pad5)") (class "Default")
      (node (ref "D2") (pin "5") (pinfunction "P1_7_5") (pintype "passive+no_connect"))
    )
    (net (code "76") (name "unconnected-(D2-P2_7-Pad15)") (class "Default")
      (node (ref "D2") (pin "15") (pinfunction "P2_7_15") (pintype "passive+no_connect"))
    )
    (net (code "77") (name "unconnected-(D2-P3_6-Pad9)") (class "Default")
      (node (ref "D2") (pin "9") (pinfunction "P3_6_9") (pintype "passive+no_connect"))
    )
  )
)
